# MacroPad.net
KiCad netlist of a schematic drawn in EAGLE
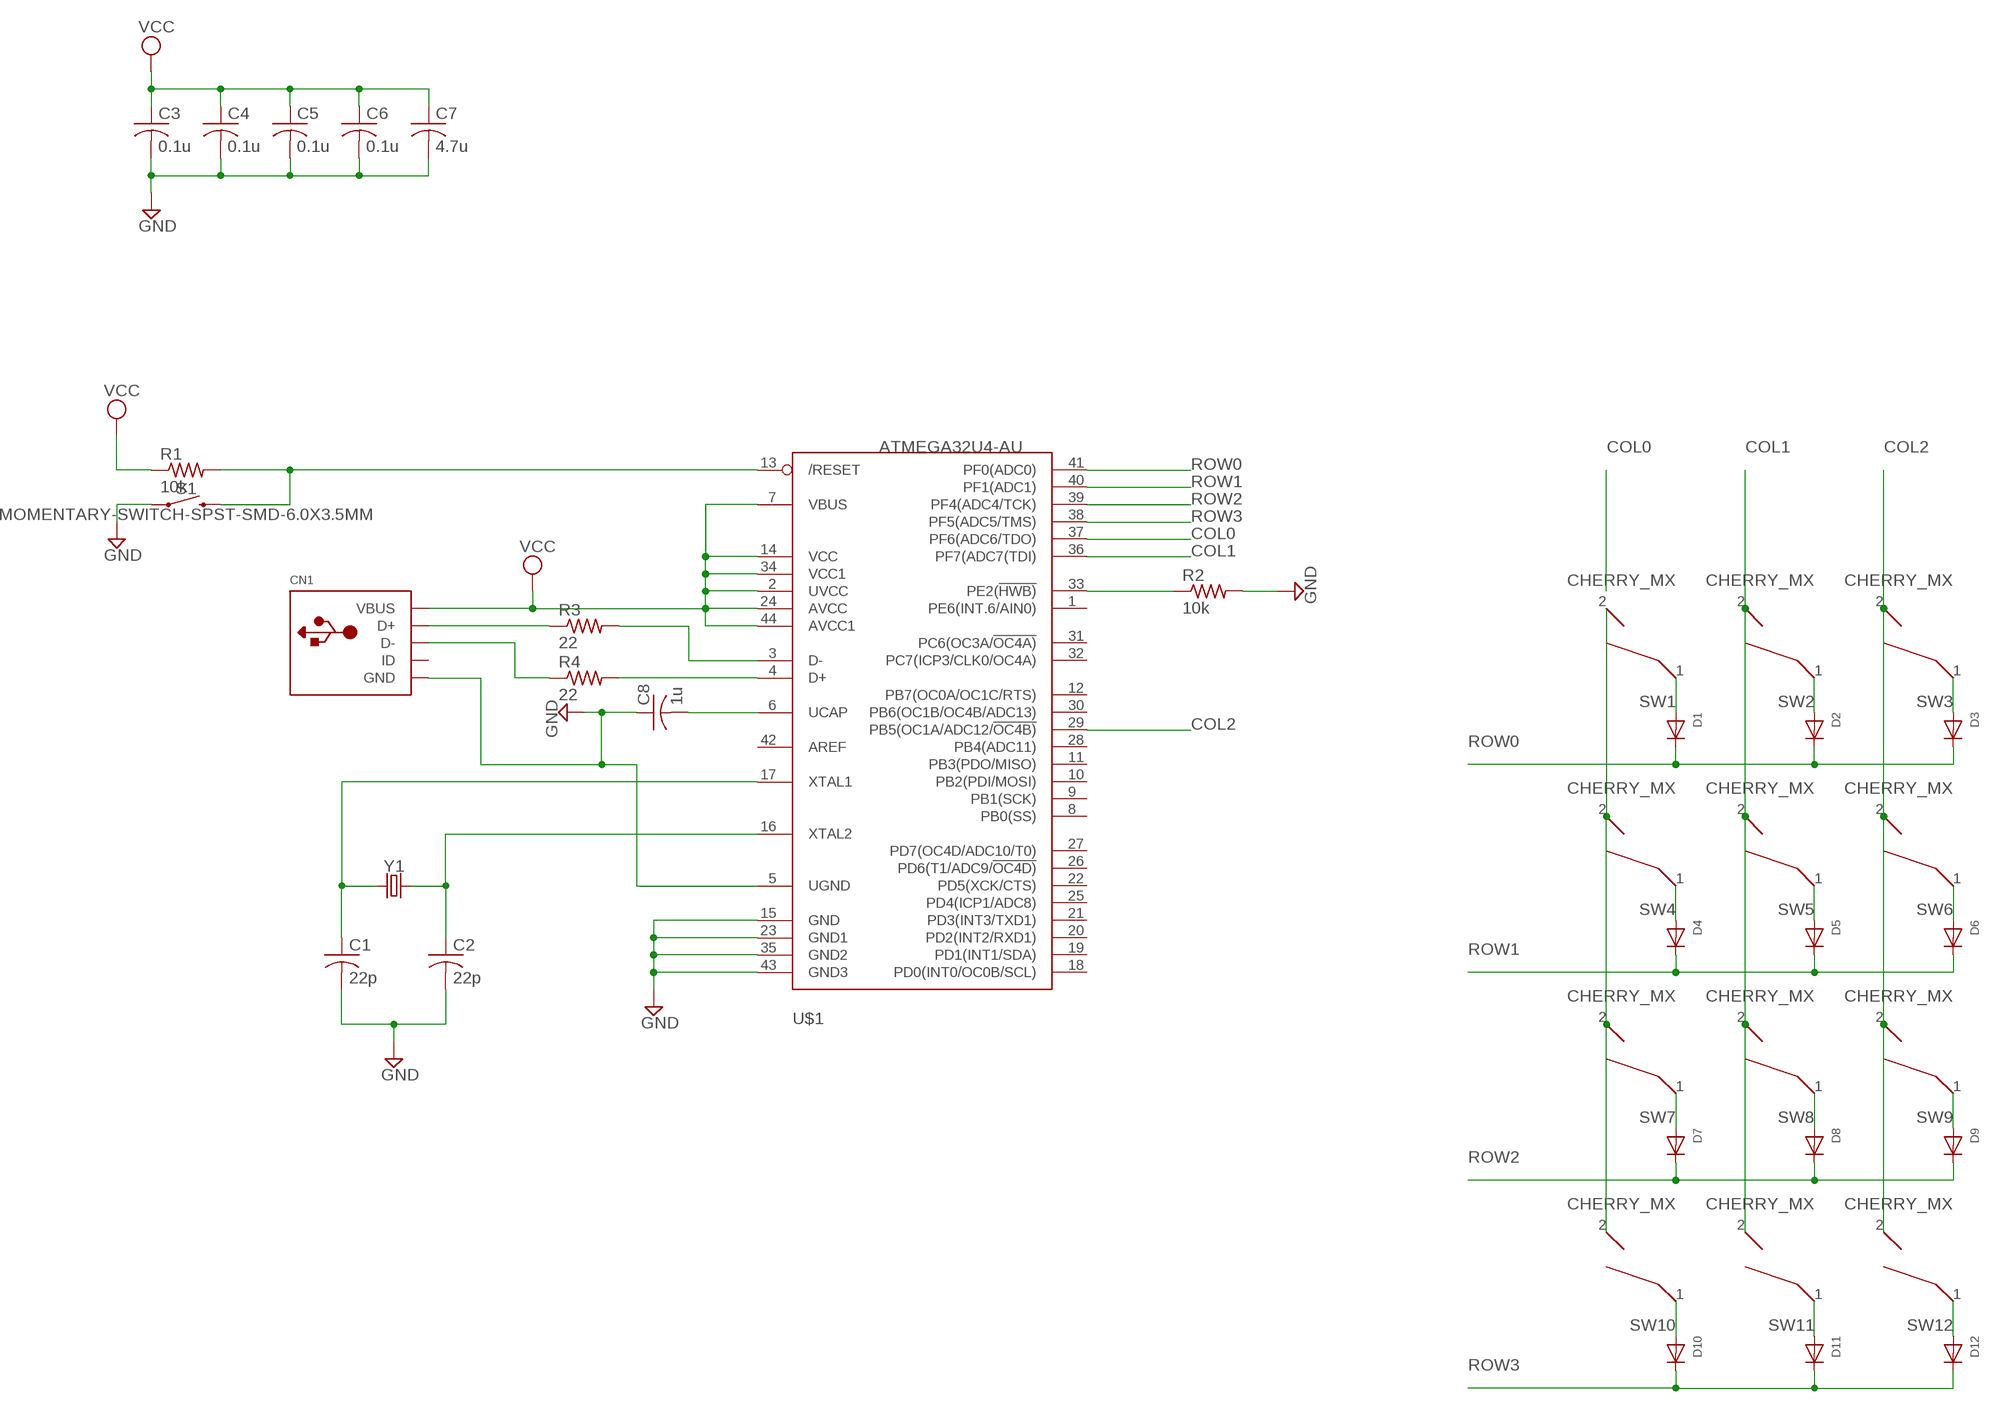
[diagram p0: schematic, sheet 1]

(export (version "E")
  (design (tool "Eeschema 10.0.6"))
  (components
    (comp (ref "C1")
      (value "22p")
      (footprint "eagle-import:C0805")
      (libsource (lib "eagle-import") (part "C-USC0805"))
    )
    (comp (ref "C2")
      (value "22p")
      (footprint "eagle-import:C0805")
      (libsource (lib "eagle-import") (part "C-USC0805"))
    )
    (comp (ref "C3")
      (value "0.1u")
      (footprint "eagle-import:C0805")
      (libsource (lib "eagle-import") (part "C-USC0805"))
    )
    (comp (ref "C4")
      (value "0.1u")
      (footprint "eagle-import:C0805")
      (libsource (lib "eagle-import") (part "C-USC0805"))
    )
    (comp (ref "C5")
      (value "0.1u")
      (footprint "eagle-import:C0805")
      (libsource (lib "eagle-import") (part "C-USC0805"))
    )
    (comp (ref "C6")
      (value "0.1u")
      (footprint "eagle-import:C0805")
      (libsource (lib "eagle-import") (part "C-USC0805"))
    )
    (comp (ref "C7")
      (value "4.7u")
      (footprint "eagle-import:C0805")
      (libsource (lib "eagle-import") (part "C-USC0805"))
    )
    (comp (ref "C8")
      (value "1u")
      (footprint "eagle-import:C0805")
      (libsource (lib "eagle-import") (part "C-USC0805"))
    )
    (comp (ref "CN1")
      (value "USBMOLEX")
      (footprint "eagle-import:USB-MINIB-THM-MOLEX")
      (libsource (lib "eagle-import") (part "USBMOLEX"))
    )
    (comp (ref "D1")
      (value "DIODEDO-1N4148")
      (footprint "eagle-import:DO-1N4148")
      (libsource (lib "eagle-import") (part "DIODEDO-1N4148"))
    )
    (comp (ref "D2")
      (value "DIODEDO-1N4148")
      (footprint "eagle-import:DO-1N4148")
      (libsource (lib "eagle-import") (part "DIODEDO-1N4148"))
    )
    (comp (ref "D3")
      (value "DIODEDO-1N4148")
      (footprint "eagle-import:DO-1N4148")
      (libsource (lib "eagle-import") (part "DIODEDO-1N4148"))
    )
    (comp (ref "D4")
      (value "DIODEDO-1N4148")
      (footprint "eagle-import:DO-1N4148")
      (libsource (lib "eagle-import") (part "DIODEDO-1N4148"))
    )
    (comp (ref "D5")
      (value "DIODEDO-1N4148")
      (footprint "eagle-import:DO-1N4148")
      (libsource (lib "eagle-import") (part "DIODEDO-1N4148"))
    )
    (comp (ref "D6")
      (value "DIODEDO-1N4148")
      (footprint "eagle-import:DO-1N4148")
      (libsource (lib "eagle-import") (part "DIODEDO-1N4148"))
    )
    (comp (ref "D7")
      (value "DIODEDO-1N4148")
      (footprint "eagle-import:DO-1N4148")
      (libsource (lib "eagle-import") (part "DIODEDO-1N4148"))
    )
    (comp (ref "D8")
      (value "DIODEDO-1N4148")
      (footprint "eagle-import:DO-1N4148")
      (libsource (lib "eagle-import") (part "DIODEDO-1N4148"))
    )
    (comp (ref "D9")
      (value "DIODEDO-1N4148")
      (footprint "eagle-import:DO-1N4148")
      (libsource (lib "eagle-import") (part "DIODEDO-1N4148"))
    )
    (comp (ref "D10")
      (value "DIODEDO-1N4148")
      (footprint "eagle-import:DO-1N4148")
      (libsource (lib "eagle-import") (part "DIODEDO-1N4148"))
    )
    (comp (ref "D11")
      (value "DIODEDO-1N4148")
      (footprint "eagle-import:DO-1N4148")
      (libsource (lib "eagle-import") (part "DIODEDO-1N4148"))
    )
    (comp (ref "D12")
      (value "DIODEDO-1N4148")
      (footprint "eagle-import:DO-1N4148")
      (libsource (lib "eagle-import") (part "DIODEDO-1N4148"))
    )
    (comp (ref "R1")
      (value "10k")
      (footprint "eagle-import:R0805")
      (fields (field (name "SPICEPREFIX") "R"))
      (libsource (lib "eagle-import") (part "R-US_R0805"))
    )
    (comp (ref "R2")
      (value "10k")
      (footprint "eagle-import:R0805")
      (libsource (lib "eagle-import") (part "R-US_R0805"))
    )
    (comp (ref "R3")
      (value "22")
      (footprint "eagle-import:R0805")
      (fields (field (name "SPICEPREFIX") "R"))
      (libsource (lib "eagle-import") (part "R-US_R0805"))
    )
    (comp (ref "R4")
      (value "22")
      (footprint "eagle-import:R0805")
      (fields (field (name "SPICEPREFIX") "R"))
      (libsource (lib "eagle-import") (part "R-US_R0805"))
    )
    (comp (ref "S1")
      (value "MOMENTARY-SWITCH-SPST-SMD-6.0X3.5MM")
      (footprint "eagle-import:TACTILE_SWITCH_SMD_6.0X3.5MM")
      (fields (field (name "SPICEPREFIX") "B"))
      (libsource (lib "eagle-import") (part "MOMENTARY-SWITCH-SPST-SMD-6.0X3.5MM"))
    )
    (comp (ref "SW1")
      (value "CHERRY_MX")
      (footprint "eagle-import:MX1A-XXNN")
      (libsource (lib "eagle-import") (part "CHERRY_MX"))
    )
    (comp (ref "SW2")
      (value "CHERRY_MX")
      (footprint "eagle-import:MX1A-XXNN")
      (libsource (lib "eagle-import") (part "CHERRY_MX"))
    )
    (comp (ref "SW3")
      (value "CHERRY_MX")
      (footprint "eagle-import:MX1A-XXNN")
      (libsource (lib "eagle-import") (part "CHERRY_MX"))
    )
    (comp (ref "SW4")
      (value "CHERRY_MX")
      (footprint "eagle-import:MX1A-XXNN")
      (libsource (lib "eagle-import") (part "CHERRY_MX"))
    )
    (comp (ref "SW5")
      (value "CHERRY_MX")
      (footprint "eagle-import:MX1A-XXNN")
      (libsource (lib "eagle-import") (part "CHERRY_MX"))
    )
    (comp (ref "SW6")
      (value "CHERRY_MX")
      (footprint "eagle-import:MX1A-XXNN")
      (libsource (lib "eagle-import") (part "CHERRY_MX"))
    )
    (comp (ref "SW7")
      (value "CHERRY_MX")
      (footprint "eagle-import:MX1A-XXNN")
      (libsource (lib "eagle-import") (part "CHERRY_MX"))
    )
    (comp (ref "SW8")
      (value "CHERRY_MX")
      (footprint "eagle-import:MX1A-XXNN")
      (libsource (lib "eagle-import") (part "CHERRY_MX"))
    )
    (comp (ref "SW9")
      (value "CHERRY_MX")
      (footprint "eagle-import:MX1A-XXNN")
      (libsource (lib "eagle-import") (part "CHERRY_MX"))
    )
    (comp (ref "SW10")
      (value "CHERRY_MX")
      (footprint "eagle-import:MX1A-XXNN")
      (libsource (lib "eagle-import") (part "CHERRY_MX"))
    )
    (comp (ref "SW11")
      (value "CHERRY_MX")
      (footprint "eagle-import:MX1A-XXNN")
      (libsource (lib "eagle-import") (part "CHERRY_MX"))
    )
    (comp (ref "SW12")
      (value "CHERRY_MX")
      (footprint "eagle-import:MX1A-XXNN")
      (libsource (lib "eagle-import") (part "CHERRY_MX"))
    )
    (comp (ref "U$1")
      (value "ATMEGA32U4-AU")
      (footprint "eagle-import:TQFP44")
      (libsource (lib "eagle-import") (part "ATMEGA32U4-AU"))
    )
    (comp (ref "Y1")
      (value "CRYSTALSMD-5X3.2-4PAD")
      (footprint "eagle-import:CRYSTAL-SMD-5X3.2-4PAD")
      (libsource (lib "eagle-import") (part "CRYSTALSMD-5X3.2-4PAD"))
    )
  )
  (nets
    (net (code "1") (name "/COL0") (class "Default")
      (node (ref "U$1") (pin "37") (pinfunction "PF6(ADC6/TDO)_37") (pintype "bidirectional"))
    )
    (net (code "2") (name "/COL1") (class "Default")
      (node (ref "SW11") (pin "2") (pinfunction "2_2") (pintype "passive"))
      (node (ref "SW2") (pin "2") (pinfunction "2_2") (pintype "passive"))
      (node (ref "SW5") (pin "2") (pinfunction "2_2") (pintype "passive"))
      (node (ref "SW8") (pin "2") (pinfunction "2_2") (pintype "passive"))
      (node (ref "U$1") (pin "36") (pinfunction "PF7(ADC7(TDI)_36") (pintype "bidirectional"))
    )
    (net (code "3") (name "/COL2") (class "Default")
      (node (ref "SW12") (pin "2") (pinfunction "2_2") (pintype "passive"))
      (node (ref "SW3") (pin "2") (pinfunction "2_2") (pintype "passive"))
      (node (ref "SW6") (pin "2") (pinfunction "2_2") (pintype "passive"))
      (node (ref "SW9") (pin "2") (pinfunction "2_2") (pintype "passive"))
      (node (ref "U$1") (pin "29") (pinfunction "PB5(OC1A/ADC12/~{OC4B})_29") (pintype "bidirectional"))
    )
    (net (code "4") (name "/ROW0") (class "Default")
      (node (ref "D1") (pin "C") (pinfunction "C_C") (pintype "passive"))
      (node (ref "D2") (pin "C") (pinfunction "C_C") (pintype "passive"))
      (node (ref "D3") (pin "C") (pinfunction "C_C") (pintype "passive"))
      (node (ref "U$1") (pin "41") (pinfunction "PF0(ADC0)_41") (pintype "bidirectional"))
    )
    (net (code "5") (name "/ROW1") (class "Default")
      (node (ref "D4") (pin "C") (pinfunction "C_C") (pintype "passive"))
      (node (ref "D5") (pin "C") (pinfunction "C_C") (pintype "passive"))
      (node (ref "D6") (pin "C") (pinfunction "C_C") (pintype "passive"))
      (node (ref "U$1") (pin "40") (pinfunction "PF1(ADC1)_40") (pintype "bidirectional"))
    )
    (net (code "6") (name "/ROW2") (class "Default")
      (node (ref "D7") (pin "C") (pinfunction "C_C") (pintype "passive"))
      (node (ref "D8") (pin "C") (pinfunction "C_C") (pintype "passive"))
      (node (ref "D9") (pin "C") (pinfunction "C_C") (pintype "passive"))
      (node (ref "U$1") (pin "39") (pinfunction "PF4(ADC4/TCK)_39") (pintype "bidirectional"))
    )
    (net (code "7") (name "/ROW3") (class "Default")
      (node (ref "D10") (pin "C") (pinfunction "C_C") (pintype "passive"))
      (node (ref "D11") (pin "C") (pinfunction "C_C") (pintype "passive"))
      (node (ref "D12") (pin "C") (pinfunction "C_C") (pintype "passive"))
      (node (ref "U$1") (pin "38") (pinfunction "PF5(ADC5/TMS)_38") (pintype "bidirectional"))
    )
    (net (code "8") (name "GND") (class "Default")
      (node (ref "C1") (pin "2") (pinfunction "2_2") (pintype "passive"))
      (node (ref "C2") (pin "2") (pinfunction "2_2") (pintype "passive"))
      (node (ref "C3") (pin "2") (pinfunction "2_2") (pintype "passive"))
      (node (ref "C4") (pin "2") (pinfunction "2_2") (pintype "passive"))
      (node (ref "C5") (pin "2") (pinfunction "2_2") (pintype "passive"))
      (node (ref "C6") (pin "2") (pinfunction "2_2") (pintype "passive"))
      (node (ref "C7") (pin "2") (pinfunction "2_2") (pintype "passive"))
      (node (ref "C8") (pin "1") (pinfunction "1_1") (pintype "passive"))
      (node (ref "CN1") (pin "GND") (pinfunction "GND_GND") (pintype "power_in"))
      (node (ref "R2") (pin "2") (pinfunction "2_2") (pintype "passive"))
      (node (ref "S1") (pin "1") (pinfunction "1_1") (pintype "passive"))
      (node (ref "U$1") (pin "15") (pinfunction "GND_15") (pintype "bidirectional"))
      (node (ref "U$1") (pin "23") (pinfunction "GND1_23") (pintype "bidirectional"))
      (node (ref "U$1") (pin "35") (pinfunction "GND2_35") (pintype "bidirectional"))
      (node (ref "U$1") (pin "43") (pinfunction "GND3_43") (pintype "bidirectional"))
      (node (ref "U$1") (pin "5") (pinfunction "UGND_5") (pintype "bidirectional"))
    )
    (net (code "9") (name "Net-(CN1-PadD+)") (class "Default")
      (node (ref "CN1") (pin "D+") (pinfunction "D+_D+") (pintype "bidirectional"))
      (node (ref "R3") (pin "1") (pinfunction "1_1") (pintype "passive"))
    )
    (net (code "10") (name "Net-(CN1-PadD-)") (class "Default")
      (node (ref "CN1") (pin "D-") (pinfunction "D-_D-") (pintype "bidirectional"))
      (node (ref "R4") (pin "1") (pinfunction "1_1") (pintype "passive"))
    )
    (net (code "11") (name "Net-(D1-PadA)") (class "Default")
      (node (ref "D1") (pin "A") (pinfunction "A_A") (pintype "passive"))
      (node (ref "SW1") (pin "1") (pinfunction "1_1") (pintype "passive"))
    )
    (net (code "12") (name "Net-(D2-PadA)") (class "Default")
      (node (ref "D2") (pin "A") (pinfunction "A_A") (pintype "passive"))
      (node (ref "SW2") (pin "1") (pinfunction "1_1") (pintype "passive"))
    )
    (net (code "13") (name "Net-(D3-PadA)") (class "Default")
      (node (ref "D3") (pin "A") (pinfunction "A_A") (pintype "passive"))
      (node (ref "SW3") (pin "1") (pinfunction "1_1") (pintype "passive"))
    )
    (net (code "14") (name "Net-(D4-PadA)") (class "Default")
      (node (ref "D4") (pin "A") (pinfunction "A_A") (pintype "passive"))
      (node (ref "SW4") (pin "1") (pinfunction "1_1") (pintype "passive"))
    )
    (net (code "15") (name "Net-(D5-PadA)") (class "Default")
      (node (ref "D5") (pin "A") (pinfunction "A_A") (pintype "passive"))
      (node (ref "SW5") (pin "1") (pinfunction "1_1") (pintype "passive"))
    )
    (net (code "16") (name "Net-(D6-PadA)") (class "Default")
      (node (ref "D6") (pin "A") (pinfunction "A_A") (pintype "passive"))
      (node (ref "SW6") (pin "1") (pinfunction "1_1") (pintype "passive"))
    )
    (net (code "17") (name "Net-(D7-PadA)") (class "Default")
      (node (ref "D7") (pin "A") (pinfunction "A_A") (pintype "passive"))
      (node (ref "SW7") (pin "1") (pinfunction "1_1") (pintype "passive"))
    )
    (net (code "18") (name "Net-(D8-PadA)") (class "Default")
      (node (ref "D8") (pin "A") (pinfunction "A_A") (pintype "passive"))
      (node (ref "SW8") (pin "1") (pinfunction "1_1") (pintype "passive"))
    )
    (net (code "19") (name "Net-(D9-PadA)") (class "Default")
      (node (ref "D9") (pin "A") (pinfunction "A_A") (pintype "passive"))
      (node (ref "SW9") (pin "1") (pinfunction "1_1") (pintype "passive"))
    )
    (net (code "20") (name "Net-(D10-PadA)") (class "Default")
      (node (ref "D10") (pin "A") (pinfunction "A_A") (pintype "passive"))
      (node (ref "SW10") (pin "1") (pinfunction "1_1") (pintype "passive"))
    )
    (net (code "21") (name "Net-(D11-PadA)") (class "Default")
      (node (ref "D11") (pin "A") (pinfunction "A_A") (pintype "passive"))
      (node (ref "SW11") (pin "1") (pinfunction "1_1") (pintype "passive"))
    )
    (net (code "22") (name "Net-(D12-PadA)") (class "Default")
      (node (ref "D12") (pin "A") (pinfunction "A_A") (pintype "passive"))
      (node (ref "SW12") (pin "1") (pinfunction "1_1") (pintype "passive"))
    )
    (net (code "23") (name "Net-(SW1-Pad2)") (class "Default")
      (node (ref "SW1") (pin "2") (pinfunction "2_2") (pintype "passive"))
      (node (ref "SW10") (pin "2") (pinfunction "2_2") (pintype "passive"))
      (node (ref "SW4") (pin "2") (pinfunction "2_2") (pintype "passive"))
      (node (ref "SW7") (pin "2") (pinfunction "2_2") (pintype "passive"))
    )
    (net (code "24") (name "Net-(U$1-D+)") (class "Default")
      (node (ref "R4") (pin "2") (pinfunction "2_2") (pintype "passive"))
      (node (ref "U$1") (pin "4") (pinfunction "D+_4") (pintype "bidirectional"))
    )
    (net (code "25") (name "Net-(U$1-D-)") (class "Default")
      (node (ref "R3") (pin "2") (pinfunction "2_2") (pintype "passive"))
      (node (ref "U$1") (pin "3") (pinfunction "D-_3") (pintype "bidirectional"))
    )
    (net (code "26") (name "Net-(U$1-PE2(~{HWB}))") (class "Default")
      (node (ref "R2") (pin "1") (pinfunction "1_1") (pintype "passive"))
      (node (ref "U$1") (pin "33") (pinfunction "PE2(~{HWB})_33") (pintype "bidirectional"))
    )
    (net (code "27") (name "Net-(U$1-UCAP)") (class "Default")
      (node (ref "C8") (pin "2") (pinfunction "2_2") (pintype "passive"))
      (node (ref "U$1") (pin "6") (pinfunction "UCAP_6") (pintype "bidirectional"))
    )
    (net (code "28") (name "Net-(U$1-XTAL1)") (class "Default")
      (node (ref "C1") (pin "1") (pinfunction "1_1") (pintype "passive"))
      (node (ref "U$1") (pin "17") (pinfunction "XTAL1_17") (pintype "bidirectional"))
      (node (ref "Y1") (pin "1") (pinfunction "1_1") (pintype "passive"))
    )
    (net (code "29") (name "Net-(U$1-XTAL2)") (class "Default")
      (node (ref "C2") (pin "1") (pinfunction "1_1") (pintype "passive"))
      (node (ref "U$1") (pin "16") (pinfunction "XTAL2_16") (pintype "bidirectional"))
      (node (ref "Y1") (pin "3") (pinfunction "2_3") (pintype "passive"))
    )
    (net (code "30") (name "Net-(U$1-{slash}RESET)") (class "Default")
      (node (ref "R1") (pin "2") (pinfunction "2_2") (pintype "passive"))
      (node (ref "S1") (pin "2") (pinfunction "2_2") (pintype "passive"))
      (node (ref "U$1") (pin "13") (pinfunction "/RESET_13") (pintype "bidirectional"))
    )
    (net (code "31") (name "VCC") (class "Default")
      (node (ref "C3") (pin "1") (pinfunction "1_1") (pintype "passive"))
      (node (ref "C4") (pin "1") (pinfunction "1_1") (pintype "passive"))
      (node (ref "C5") (pin "1") (pinfunction "1_1") (pintype "passive"))
      (node (ref "C6") (pin "1") (pinfunction "1_1") (pintype "passive"))
      (node (ref "C7") (pin "1") (pinfunction "1_1") (pintype "passive"))
      (node (ref "CN1") (pin "VBUS") (pinfunction "VBUS_VBUS") (pintype "power_in"))
      (node (ref "R1") (pin "1") (pinfunction "1_1") (pintype "passive"))
      (node (ref "U$1") (pin "14") (pinfunction "VCC_14") (pintype "bidirectional"))
      (node (ref "U$1") (pin "2") (pinfunction "UVCC_2") (pintype "bidirectional"))
      (node (ref "U$1") (pin "24") (pinfunction "AVCC_24") (pintype "bidirectional"))
      (node (ref "U$1") (pin "34") (pinfunction "VCC1_34") (pintype "bidirectional"))
      (node (ref "U$1") (pin "44") (pinfunction "AVCC1_44") (pintype "bidirectional"))
      (node (ref "U$1") (pin "7") (pinfunction "VBUS_7") (pintype "bidirectional"))
    )
    (net (code "32") (name "unconnected-(CN1-PadID)") (class "Default")
      (node (ref "CN1") (pin "ID") (pinfunction "ID_ID") (pintype "bidirectional"))
    )
    (net (code "33") (name "unconnected-(U$1-AREF-Pad42)") (class "Default")
      (node (ref "U$1") (pin "42") (pinfunction "AREF_42") (pintype "bidirectional"))
    )
    (net (code "34") (name "unconnected-(U$1-PB0(SS)-Pad8)") (class "Default")
      (node (ref "U$1") (pin "8") (pinfunction "PB0(SS)_8") (pintype "bidirectional"))
    )
    (net (code "35") (name "unconnected-(U$1-PB1(SCK)-Pad9)") (class "Default")
      (node (ref "U$1") (pin "9") (pinfunction "PB1(SCK)_9") (pintype "bidirectional"))
    )
    (net (code "36") (name "unconnected-(U$1-PB2(PDI{slash}MOSI)-Pad10)") (class "Default")
      (node (ref "U$1") (pin "10") (pinfunction "PB2(PDI/MOSI)_10") (pintype "bidirectional"))
    )
    (net (code "37") (name "unconnected-(U$1-PB3(PDO{slash}MISO)-Pad11)") (class "Default")
      (node (ref "U$1") (pin "11") (pinfunction "PB3(PDO/MISO)_11") (pintype "bidirectional"))
    )
    (net (code "38") (name "unconnected-(U$1-PB4(ADC11)-Pad28)") (class "Default")
      (node (ref "U$1") (pin "28") (pinfunction "PB4(ADC11)_28") (pintype "bidirectional"))
    )
    (net (code "39") (name "unconnected-(U$1-PB6(OC1B{slash}OC4B{slash}ADC13)-Pad30)") (class "Default")
      (node (ref "U$1") (pin "30") (pinfunction "PB6(OC1B/OC4B/ADC13)_30") (pintype "bidirectional"))
    )
    (net (code "40") (name "unconnected-(U$1-PB7(OC0A{slash}OC1C{slash}RTS)-Pad12)") (class "Default")
      (node (ref "U$1") (pin "12") (pinfunction "PB7(OC0A/OC1C/RTS)_12") (pintype "bidirectional"))
    )
    (net (code "41") (name "unconnected-(U$1-PC6(OC3A{slash}~{OC4A})-Pad31)") (class "Default")
      (node (ref "U$1") (pin "31") (pinfunction "PC6(OC3A/~{OC4A})_31") (pintype "bidirectional"))
    )
    (net (code "42") (name "unconnected-(U$1-PC7(ICP3{slash}CLK0{slash}OC4A)-Pad32)") (class "Default")
      (node (ref "U$1") (pin "32") (pinfunction "PC7(ICP3/CLK0/OC4A)_32") (pintype "bidirectional"))
    )
    (net (code "43") (name "unconnected-(U$1-PD0(INT0{slash}OC0B{slash}SCL)-Pad18)") (class "Default")
      (node (ref "U$1") (pin "18") (pinfunction "PD0(INT0/OC0B/SCL)_18") (pintype "bidirectional"))
    )
    (net (code "44") (name "unconnected-(U$1-PD1(INT1{slash}SDA)-Pad19)") (class "Default")
      (node (ref "U$1") (pin "19") (pinfunction "PD1(INT1/SDA)_19") (pintype "bidirectional"))
    )
    (net (code "45") (name "unconnected-(U$1-PD2(INT2{slash}RXD1)-Pad20)") (class "Default")
      (node (ref "U$1") (pin "20") (pinfunction "PD2(INT2/RXD1)_20") (pintype "bidirectional"))
    )
    (net (code "46") (name "unconnected-(U$1-PD3(INT3{slash}TXD1)-Pad21)") (class "Default")
      (node (ref "U$1") (pin "21") (pinfunction "PD3(INT3/TXD1)_21") (pintype "bidirectional"))
    )
    (net (code "47") (name "unconnected-(U$1-PD4(ICP1{slash}ADC8)-Pad25)") (class "Default")
      (node (ref "U$1") (pin "25") (pinfunction "PD4(ICP1/ADC8)_25") (pintype "bidirectional"))
    )
    (net (code "48") (name "unconnected-(U$1-PD5(XCK{slash}CTS)-Pad22)") (class "Default")
      (node (ref "U$1") (pin "22") (pinfunction "PD5(XCK/CTS)_22") (pintype "bidirectional"))
    )
    (net (code "49") (name "unconnected-(U$1-PD6(T1{slash}ADC9{slash}~{OC4D})-Pad26)") (class "Default")
      (node (ref "U$1") (pin "26") (pinfunction "PD6(T1/ADC9/~{OC4D})_26") (pintype "bidirectional"))
    )
    (net (code "50") (name "unconnected-(U$1-PD7(OC4D{slash}ADC10{slash}T0)-Pad27)") (class "Default")
      (node (ref "U$1") (pin "27") (pinfunction "PD7(OC4D/ADC10/T0)_27") (pintype "bidirectional"))
    )
    (net (code "51") (name "unconnected-(U$1-PE6(INT.6{slash}AIN0)-Pad1)") (class "Default")
      (node (ref "U$1") (pin "1") (pinfunction "PE6(INT.6/AIN0)_1") (pintype "bidirectional"))
    )
  )
)
